# FPGA_IO.net
KiCad netlist of a schematic drawn in Altium Designer
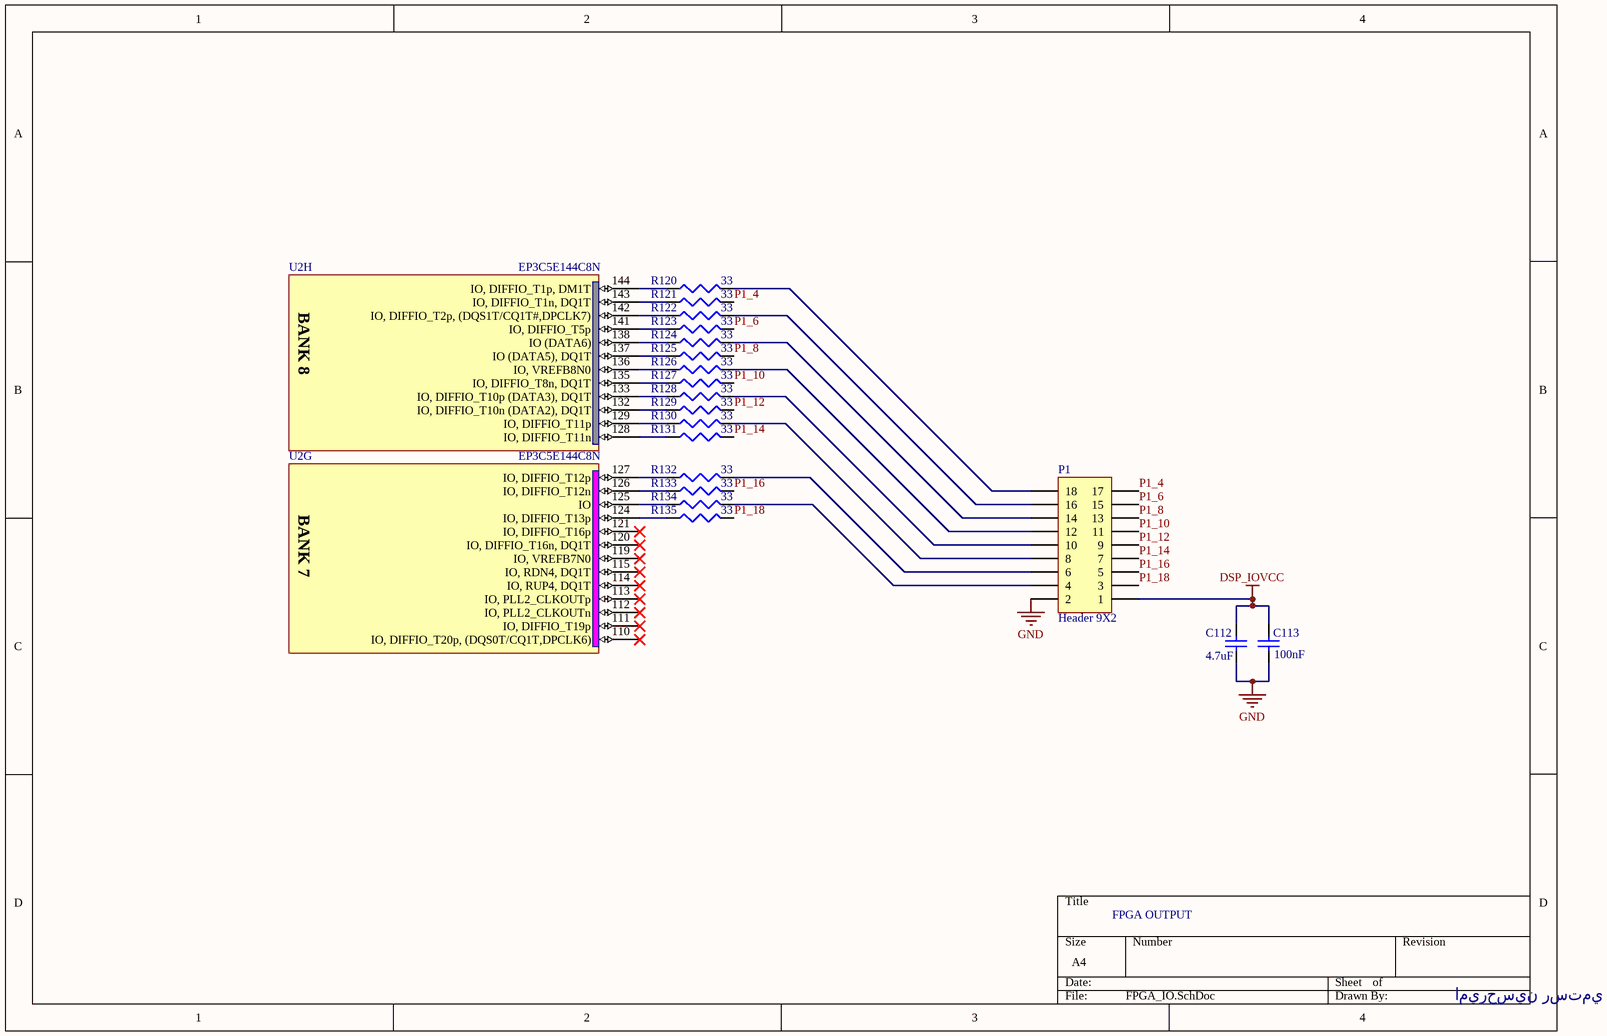
[diagram p0: FPGA_IO.SchDoc]

(export (version "E")
  (design (tool "Eeschema 10.0.6"))
  (components
    (comp (ref "C112")
      (value "4.7uF")
      (footprint "1608[0603]")
      (description "Capacitor")
      (fields (field (name "PUBLISHER") "Altium Limited"))
      (libsource (lib "Miscellaneous Devices") (part "Cap Semi"))
    )
    (comp (ref "C113")
      (value "100nF")
      (footprint "1608[0603]")
      (description "Capacitor")
      (fields (field (name "PUBLISHER") "Altium Limited"))
      (libsource (lib "Miscellaneous Devices") (part "Cap Semi"))
    )
    (comp (ref "P1")
      (value "Header 9X2")
      (footprint "HDR2X9")
      (description "Header, 9-Pin, Dual row")
      (fields (field (name "PUBLISHER") "Altium Limited"))
      (libsource (lib "Miscellaneous Connectors") (part "Header 9X2"))
    )
    (comp (ref "R120")
      (value "33")
      (footprint "J1-0603")
      (description "Resistor")
      (fields (field (name "PUBLISHER") "Altium Limited"))
      (libsource (lib "Miscellaneous Devices") (part "Res3"))
    )
    (comp (ref "R121")
      (value "33")
      (footprint "J1-0603")
      (description "Resistor")
      (fields (field (name "PUBLISHER") "Altium Limited"))
      (libsource (lib "Miscellaneous Devices") (part "Res3"))
    )
    (comp (ref "R122")
      (value "33")
      (footprint "J1-0603")
      (description "Resistor")
      (fields (field (name "PUBLISHER") "Altium Limited"))
      (libsource (lib "Miscellaneous Devices") (part "Res3"))
    )
    (comp (ref "R123")
      (value "33")
      (footprint "J1-0603")
      (description "Resistor")
      (fields (field (name "PUBLISHER") "Altium Limited"))
      (libsource (lib "Miscellaneous Devices") (part "Res3"))
    )
    (comp (ref "R124")
      (value "33")
      (footprint "J1-0603")
      (description "Resistor")
      (fields (field (name "PUBLISHER") "Altium Limited"))
      (libsource (lib "Miscellaneous Devices") (part "Res3"))
    )
    (comp (ref "R125")
      (value "33")
      (footprint "J1-0603")
      (description "Resistor")
      (fields (field (name "PUBLISHER") "Altium Limited"))
      (libsource (lib "Miscellaneous Devices") (part "Res3"))
    )
    (comp (ref "R126")
      (value "33")
      (footprint "J1-0603")
      (description "Resistor")
      (fields (field (name "PUBLISHER") "Altium Limited"))
      (libsource (lib "Miscellaneous Devices") (part "Res3"))
    )
    (comp (ref "R127")
      (value "33")
      (footprint "J1-0603")
      (description "Resistor")
      (fields (field (name "PUBLISHER") "Altium Limited"))
      (libsource (lib "Miscellaneous Devices") (part "Res3"))
    )
    (comp (ref "R128")
      (value "33")
      (footprint "J1-0603")
      (description "Resistor")
      (fields (field (name "PUBLISHER") "Altium Limited"))
      (libsource (lib "Miscellaneous Devices") (part "Res3"))
    )
    (comp (ref "R129")
      (value "33")
      (footprint "J1-0603")
      (description "Resistor")
      (fields (field (name "PUBLISHER") "Altium Limited"))
      (libsource (lib "Miscellaneous Devices") (part "Res3"))
    )
    (comp (ref "R130")
      (value "33")
      (footprint "J1-0603")
      (description "Resistor")
      (fields (field (name "PUBLISHER") "Altium Limited"))
      (libsource (lib "Miscellaneous Devices") (part "Res3"))
    )
    (comp (ref "R131")
      (value "33")
      (footprint "J1-0603")
      (description "Resistor")
      (fields (field (name "PUBLISHER") "Altium Limited"))
      (libsource (lib "Miscellaneous Devices") (part "Res3"))
    )
    (comp (ref "R132")
      (value "33")
      (footprint "J1-0603")
      (description "Resistor")
      (fields (field (name "PUBLISHER") "Altium Limited"))
      (libsource (lib "Miscellaneous Devices") (part "Res3"))
    )
    (comp (ref "R133")
      (value "33")
      (footprint "J1-0603")
      (description "Resistor")
      (fields (field (name "PUBLISHER") "Altium Limited"))
      (libsource (lib "Miscellaneous Devices") (part "Res3"))
    )
    (comp (ref "R134")
      (value "33")
      (footprint "J1-0603")
      (description "Resistor")
      (fields (field (name "PUBLISHER") "Altium Limited"))
      (libsource (lib "Miscellaneous Devices") (part "Res3"))
    )
    (comp (ref "R135")
      (value "33")
      (footprint "J1-0603")
      (description "Resistor")
      (fields (field (name "PUBLISHER") "Altium Limited"))
      (libsource (lib "Miscellaneous Devices") (part "Res3"))
    )
    (comp (ref "U2")
      (value "EP3C5E144C8N")
      (footprint "EQFP144_N")
      (fields (field (name "PUBLISHER") "Altium Limited"))
      (libsource (lib "Altera Cyclone III") (part "EP3C5E144C8N"))
    )
  )
  (nets
    (net (code "1") (name "/P1_4") (class "Default")
      (node (ref "P1") (pin "17") (pinfunction "17_17") (pintype "passive"))
      (node (ref "R121") (pin "2") (pinfunction "2_2") (pintype "passive"))
    )
    (net (code "2") (name "/P1_6") (class "Default")
      (node (ref "P1") (pin "15") (pinfunction "15_15") (pintype "passive"))
      (node (ref "R123") (pin "2") (pinfunction "2_2") (pintype "passive"))
    )
    (net (code "3") (name "/P1_8") (class "Default")
      (node (ref "P1") (pin "13") (pinfunction "13_13") (pintype "passive"))
      (node (ref "R125") (pin "2") (pinfunction "2_2") (pintype "passive"))
    )
    (net (code "4") (name "/P1_10") (class "Default")
      (node (ref "P1") (pin "11") (pinfunction "11_11") (pintype "passive"))
      (node (ref "R127") (pin "2") (pinfunction "2_2") (pintype "passive"))
    )
    (net (code "5") (name "/P1_12") (class "Default")
      (node (ref "P1") (pin "9") (pinfunction "9_9") (pintype "passive"))
      (node (ref "R129") (pin "2") (pinfunction "2_2") (pintype "passive"))
    )
    (net (code "6") (name "/P1_14") (class "Default")
      (node (ref "P1") (pin "7") (pinfunction "7_7") (pintype "passive"))
      (node (ref "R131") (pin "2") (pinfunction "2_2") (pintype "passive"))
    )
    (net (code "7") (name "/P1_16") (class "Default")
      (node (ref "P1") (pin "5") (pinfunction "5_5") (pintype "passive"))
      (node (ref "R133") (pin "2") (pinfunction "2_2") (pintype "passive"))
    )
    (net (code "8") (name "/P1_18") (class "Default")
      (node (ref "P1") (pin "3") (pinfunction "3_3") (pintype "passive"))
      (node (ref "R135") (pin "2") (pinfunction "2_2") (pintype "passive"))
    )
    (net (code "9") (name "DSP_IOVCC") (class "Default")
      (node (ref "C112") (pin "2") (pinfunction "2_2") (pintype "passive"))
      (node (ref "C113") (pin "2") (pinfunction "2_2") (pintype "passive"))
      (node (ref "P1") (pin "1") (pinfunction "1_1") (pintype "passive"))
    )
    (net (code "10") (name "GND") (class "Default")
      (node (ref "C112") (pin "1") (pinfunction "1_1") (pintype "passive"))
      (node (ref "C113") (pin "1") (pinfunction "1_1") (pintype "passive"))
      (node (ref "P1") (pin "2") (pinfunction "2_2") (pintype "passive"))
    )
    (net (code "11") (name "Net-(P1-Pad4)") (class "Default")
      (node (ref "P1") (pin "4") (pinfunction "4_4") (pintype "passive"))
      (node (ref "R134") (pin "2") (pinfunction "2_2") (pintype "passive"))
    )
    (net (code "12") (name "Net-(P1-Pad6)") (class "Default")
      (node (ref "P1") (pin "6") (pinfunction "6_6") (pintype "passive"))
      (node (ref "R132") (pin "2") (pinfunction "2_2") (pintype "passive"))
    )
    (net (code "13") (name "Net-(P1-Pad8)") (class "Default")
      (node (ref "P1") (pin "8") (pinfunction "8_8") (pintype "passive"))
      (node (ref "R130") (pin "2") (pinfunction "2_2") (pintype "passive"))
    )
    (net (code "14") (name "Net-(P1-Pad10)") (class "Default")
      (node (ref "P1") (pin "10") (pinfunction "10_10") (pintype "passive"))
      (node (ref "R128") (pin "2") (pinfunction "2_2") (pintype "passive"))
    )
    (net (code "15") (name "Net-(P1-Pad12)") (class "Default")
      (node (ref "P1") (pin "12") (pinfunction "12_12") (pintype "passive"))
      (node (ref "R126") (pin "2") (pinfunction "2_2") (pintype "passive"))
    )
    (net (code "16") (name "Net-(P1-Pad14)") (class "Default")
      (node (ref "P1") (pin "14") (pinfunction "14_14") (pintype "passive"))
      (node (ref "R124") (pin "2") (pinfunction "2_2") (pintype "passive"))
    )
    (net (code "17") (name "Net-(P1-Pad16)") (class "Default")
      (node (ref "P1") (pin "16") (pinfunction "16_16") (pintype "passive"))
      (node (ref "R122") (pin "2") (pinfunction "2_2") (pintype "passive"))
    )
    (net (code "18") (name "Net-(P1-Pad18)") (class "Default")
      (node (ref "P1") (pin "18") (pinfunction "18_18") (pintype "passive"))
      (node (ref "R120") (pin "2") (pinfunction "2_2") (pintype "passive"))
    )
    (net (code "19") (name "Net-(U2G-IO)") (class "Default")
      (node (ref "R134") (pin "1") (pinfunction "1_1") (pintype "passive"))
      (node (ref "U2") (pin "125") (pinfunction "IO_125") (pintype "bidirectional"))
    )
    (net (code "20") (name "Net-(U2G-IO,_DIFFIO_T12n)") (class "Default")
      (node (ref "R133") (pin "1") (pinfunction "1_1") (pintype "passive"))
      (node (ref "U2") (pin "126") (pinfunction "IO,_DIFFIO_T12n_126") (pintype "bidirectional"))
    )
    (net (code "21") (name "Net-(U2G-IO,_DIFFIO_T12p)") (class "Default")
      (node (ref "R132") (pin "1") (pinfunction "1_1") (pintype "passive"))
      (node (ref "U2") (pin "127") (pinfunction "IO,_DIFFIO_T12p_127") (pintype "bidirectional"))
    )
    (net (code "22") (name "Net-(U2G-IO,_DIFFIO_T13p)") (class "Default")
      (node (ref "R135") (pin "1") (pinfunction "1_1") (pintype "passive"))
      (node (ref "U2") (pin "124") (pinfunction "IO,_DIFFIO_T13p_124") (pintype "bidirectional"))
    )
    (net (code "23") (name "Net-(U2H-IO,_DIFFIO_T1n,_DQ1T)") (class "Default")
      (node (ref "R121") (pin "1") (pinfunction "1_1") (pintype "passive"))
      (node (ref "U2") (pin "143") (pinfunction "IO,_DIFFIO_T1n,_DQ1T_143") (pintype "bidirectional"))
    )
    (net (code "24") (name "Net-(U2H-IO,_DIFFIO_T1p,_DM1T)") (class "Default")
      (node (ref "R120") (pin "1") (pinfunction "1_1") (pintype "passive"))
      (node (ref "U2") (pin "144") (pinfunction "IO,_DIFFIO_T1p,_DM1T_144") (pintype "bidirectional"))
    )
    (net (code "25") (name "Net-(U2H-IO,_DIFFIO_T2p,_(DQS1T{slash}CQ1T#,DPCLK7))") (class "Default")
      (node (ref "R122") (pin "1") (pinfunction "1_1") (pintype "passive"))
      (node (ref "U2") (pin "142") (pinfunction "IO,_DIFFIO_T2p,_(DQS1T/CQ1T#,DPCLK7)_142") (pintype "bidirectional"))
    )
    (net (code "26") (name "Net-(U2H-IO,_DIFFIO_T5p)") (class "Default")
      (node (ref "R123") (pin "1") (pinfunction "1_1") (pintype "passive"))
      (node (ref "U2") (pin "141") (pinfunction "IO,_DIFFIO_T5p_141") (pintype "bidirectional"))
    )
    (net (code "27") (name "Net-(U2H-IO,_DIFFIO_T8n,_DQ1T)") (class "Default")
      (node (ref "R127") (pin "1") (pinfunction "1_1") (pintype "passive"))
      (node (ref "U2") (pin "135") (pinfunction "IO,_DIFFIO_T8n,_DQ1T_135") (pintype "bidirectional"))
    )
    (net (code "28") (name "Net-(U2H-IO,_DIFFIO_T10n_(DATA2),_DQ1T)") (class "Default")
      (node (ref "R129") (pin "1") (pinfunction "1_1") (pintype "passive"))
      (node (ref "U2") (pin "132") (pinfunction "IO,_DIFFIO_T10n_(DATA2),_DQ1T_132") (pintype "bidirectional"))
    )
    (net (code "29") (name "Net-(U2H-IO,_DIFFIO_T10p_(DATA3),_DQ1T)") (class "Default")
      (node (ref "R128") (pin "1") (pinfunction "1_1") (pintype "passive"))
      (node (ref "U2") (pin "133") (pinfunction "IO,_DIFFIO_T10p_(DATA3),_DQ1T_133") (pintype "bidirectional"))
    )
    (net (code "30") (name "Net-(U2H-IO,_DIFFIO_T11n)") (class "Default")
      (node (ref "R131") (pin "1") (pinfunction "1_1") (pintype "passive"))
      (node (ref "U2") (pin "128") (pinfunction "IO,_DIFFIO_T11n_128") (pintype "bidirectional"))
    )
    (net (code "31") (name "Net-(U2H-IO,_DIFFIO_T11p)") (class "Default")
      (node (ref "R130") (pin "1") (pinfunction "1_1") (pintype "passive"))
      (node (ref "U2") (pin "129") (pinfunction "IO,_DIFFIO_T11p_129") (pintype "bidirectional"))
    )
    (net (code "32") (name "Net-(U2H-IO,_VREFB8N0)") (class "Default")
      (node (ref "R126") (pin "1") (pinfunction "1_1") (pintype "passive"))
      (node (ref "U2") (pin "136") (pinfunction "IO,_VREFB8N0_136") (pintype "bidirectional"))
    )
    (net (code "33") (name "Net-(U2H-IO_(DATA5),_DQ1T)") (class "Default")
      (node (ref "R125") (pin "1") (pinfunction "1_1") (pintype "passive"))
      (node (ref "U2") (pin "137") (pinfunction "IO_(DATA5),_DQ1T_137") (pintype "bidirectional"))
    )
    (net (code "34") (name "Net-(U2H-IO_(DATA6))") (class "Default")
      (node (ref "R124") (pin "1") (pinfunction "1_1") (pintype "passive"))
      (node (ref "U2") (pin "138") (pinfunction "IO_(DATA6)_138") (pintype "bidirectional"))
    )
    (net (code "35") (name "unconnected-(U2G-IO,_DIFFIO_T16n,_DQ1T-Pad120)") (class "Default")
      (node (ref "U2") (pin "120") (pinfunction "IO,_DIFFIO_T16n,_DQ1T_120") (pintype "bidirectional+no_connect"))
    )
    (net (code "36") (name "unconnected-(U2G-IO,_DIFFIO_T16p-Pad121)") (class "Default")
      (node (ref "U2") (pin "121") (pinfunction "IO,_DIFFIO_T16p_121") (pintype "bidirectional+no_connect"))
    )
    (net (code "37") (name "unconnected-(U2G-IO,_DIFFIO_T19p-Pad111)") (class "Default")
      (node (ref "U2") (pin "111") (pinfunction "IO,_DIFFIO_T19p_111") (pintype "bidirectional+no_connect"))
    )
    (net (code "38") (name "unconnected-(U2G-IO,_DIFFIO_T20p,_(DQS0T{slash}CQ1T,DPCLK6)-Pad110)") (class "Default")
      (node (ref "U2") (pin "110") (pinfunction "IO,_DIFFIO_T20p,_(DQS0T/CQ1T,DPCLK6)_110") (pintype "bidirectional+no_connect"))
    )
    (net (code "39") (name "unconnected-(U2G-IO,_PLL2_CLKOUTn-Pad112)") (class "Default")
      (node (ref "U2") (pin "112") (pinfunction "IO,_PLL2_CLKOUTn_112") (pintype "bidirectional+no_connect"))
    )
    (net (code "40") (name "unconnected-(U2G-IO,_PLL2_CLKOUTp-Pad113)") (class "Default")
      (node (ref "U2") (pin "113") (pinfunction "IO,_PLL2_CLKOUTp_113") (pintype "bidirectional+no_connect"))
    )
    (net (code "41") (name "unconnected-(U2G-IO,_RDN4,_DQ1T-Pad115)") (class "Default")
      (node (ref "U2") (pin "115") (pinfunction "IO,_RDN4,_DQ1T_115") (pintype "bidirectional+no_connect"))
    )
    (net (code "42") (name "unconnected-(U2G-IO,_RUP4,_DQ1T-Pad114)") (class "Default")
      (node (ref "U2") (pin "114") (pinfunction "IO,_RUP4,_DQ1T_114") (pintype "bidirectional+no_connect"))
    )
    (net (code "43") (name "unconnected-(U2G-IO,_VREFB7N0-Pad119)") (class "Default")
      (node (ref "U2") (pin "119") (pinfunction "IO,_VREFB7N0_119") (pintype "bidirectional+no_connect"))
    )
  )
)
